# 2.net
KiCad netlist of a schematic drawn in Altium Designer
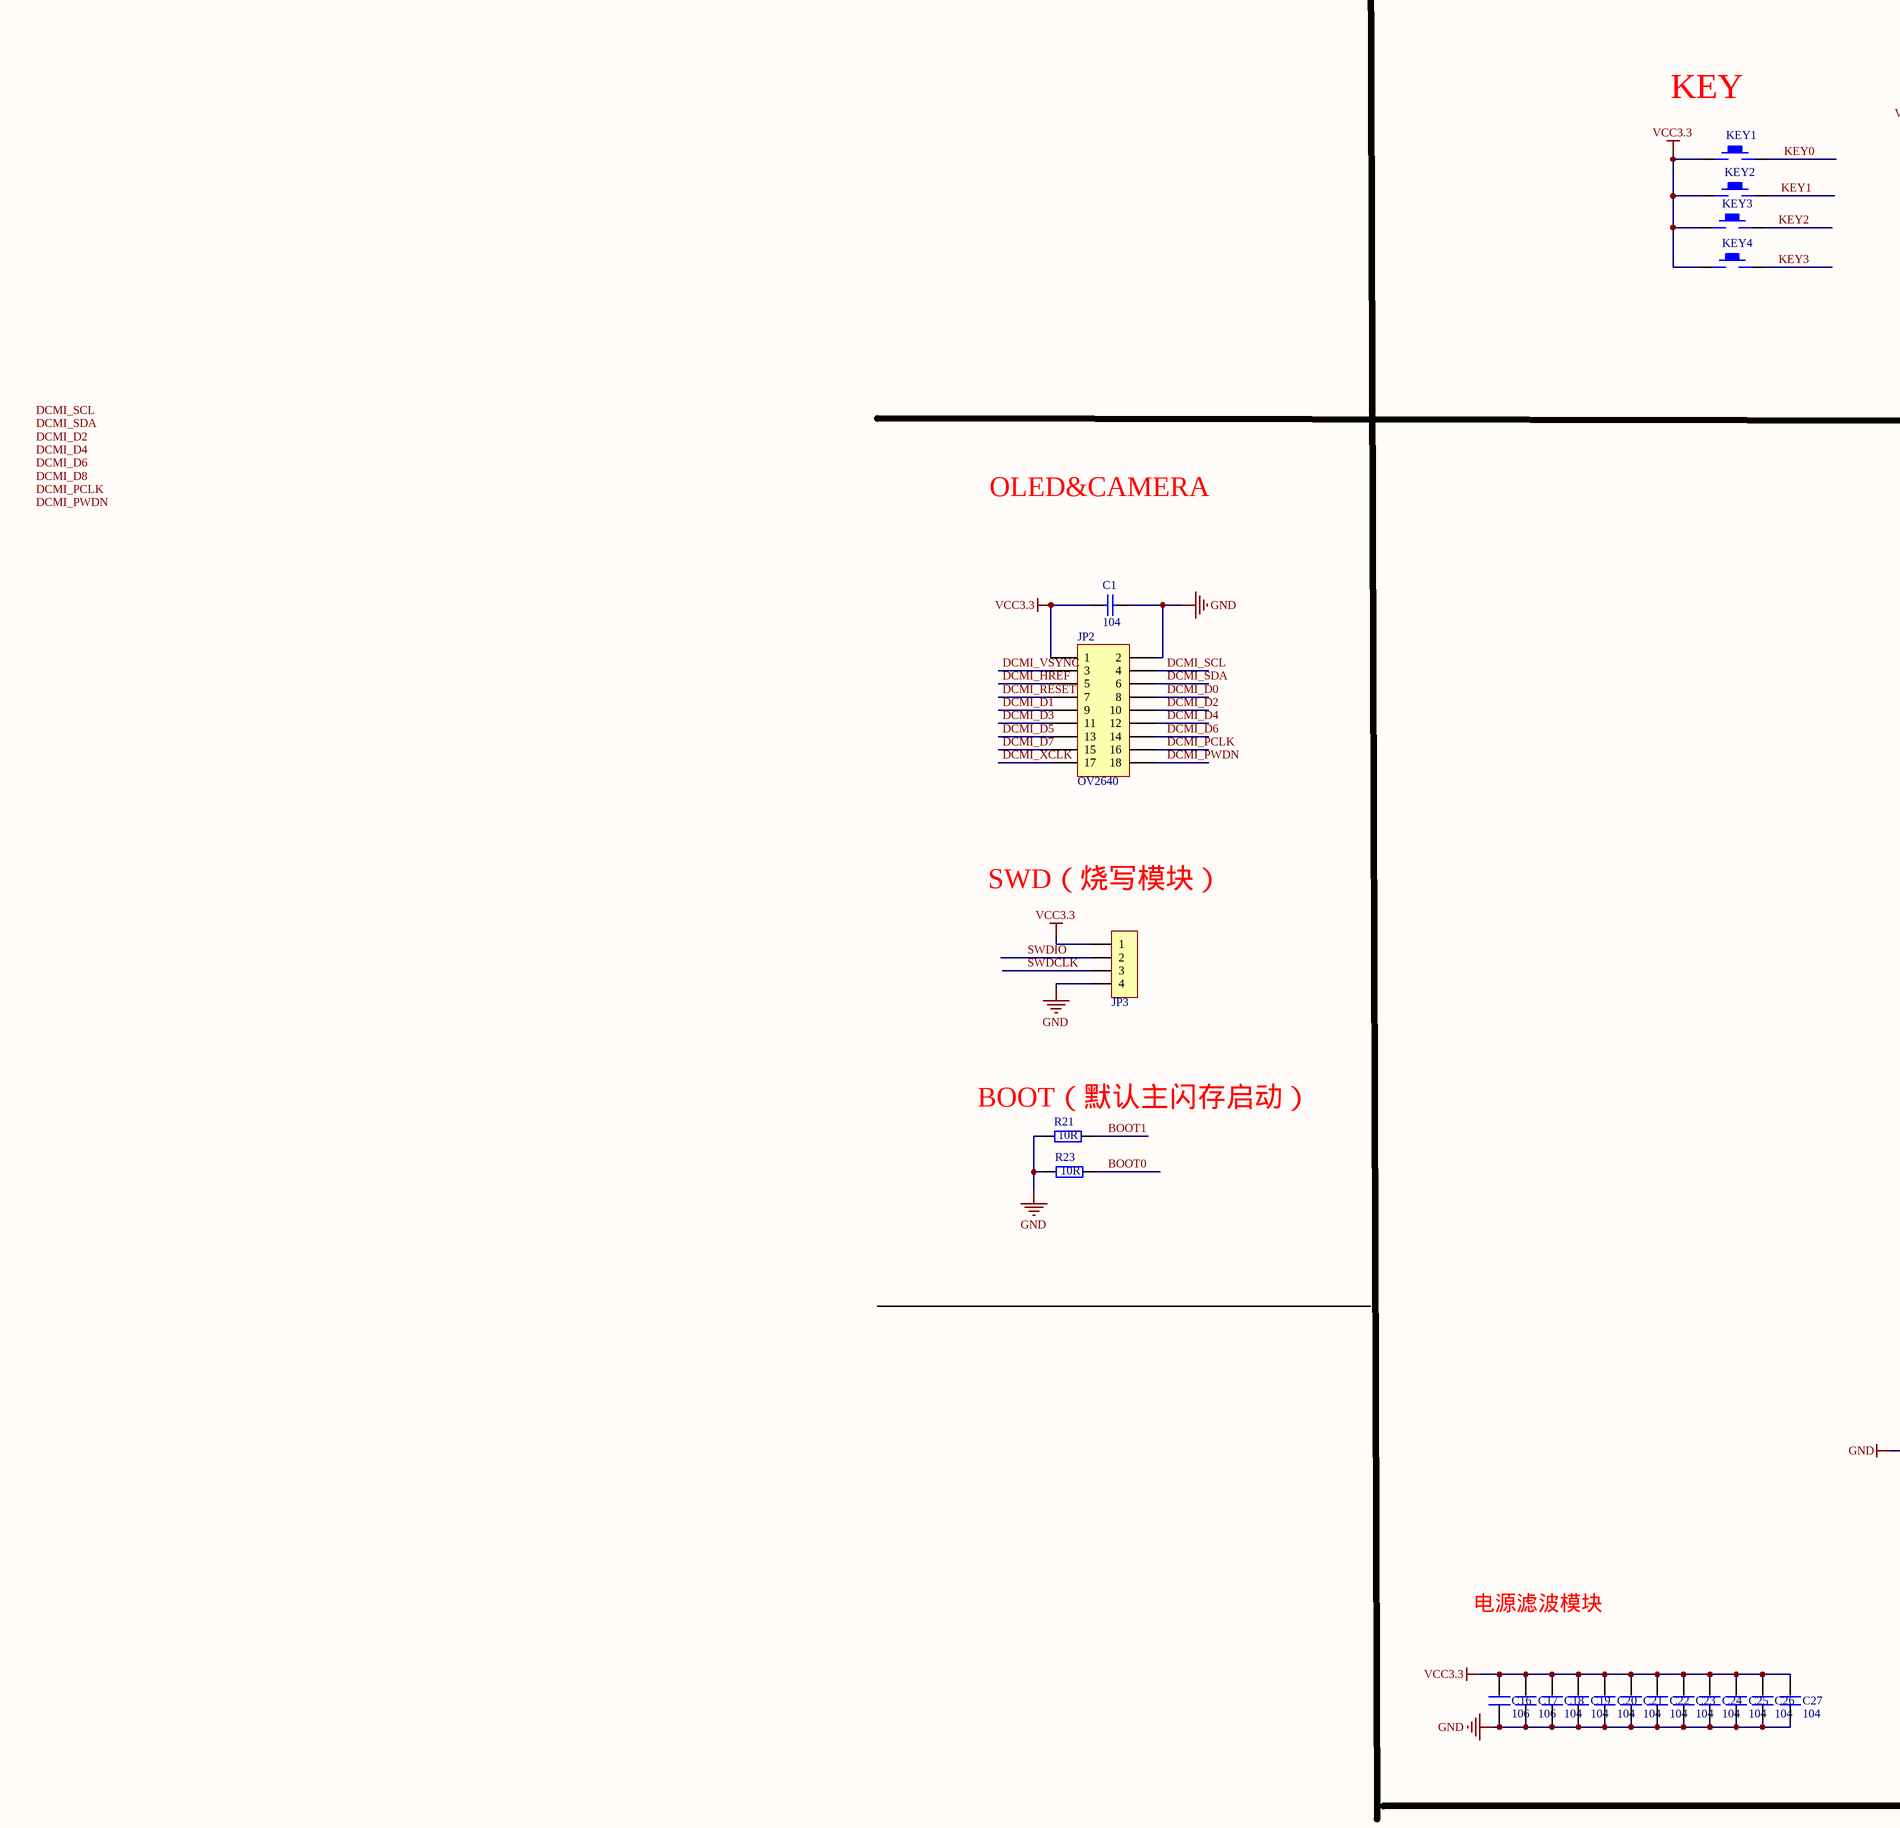
[diagram p0: 练一练2.SchDoc, left]
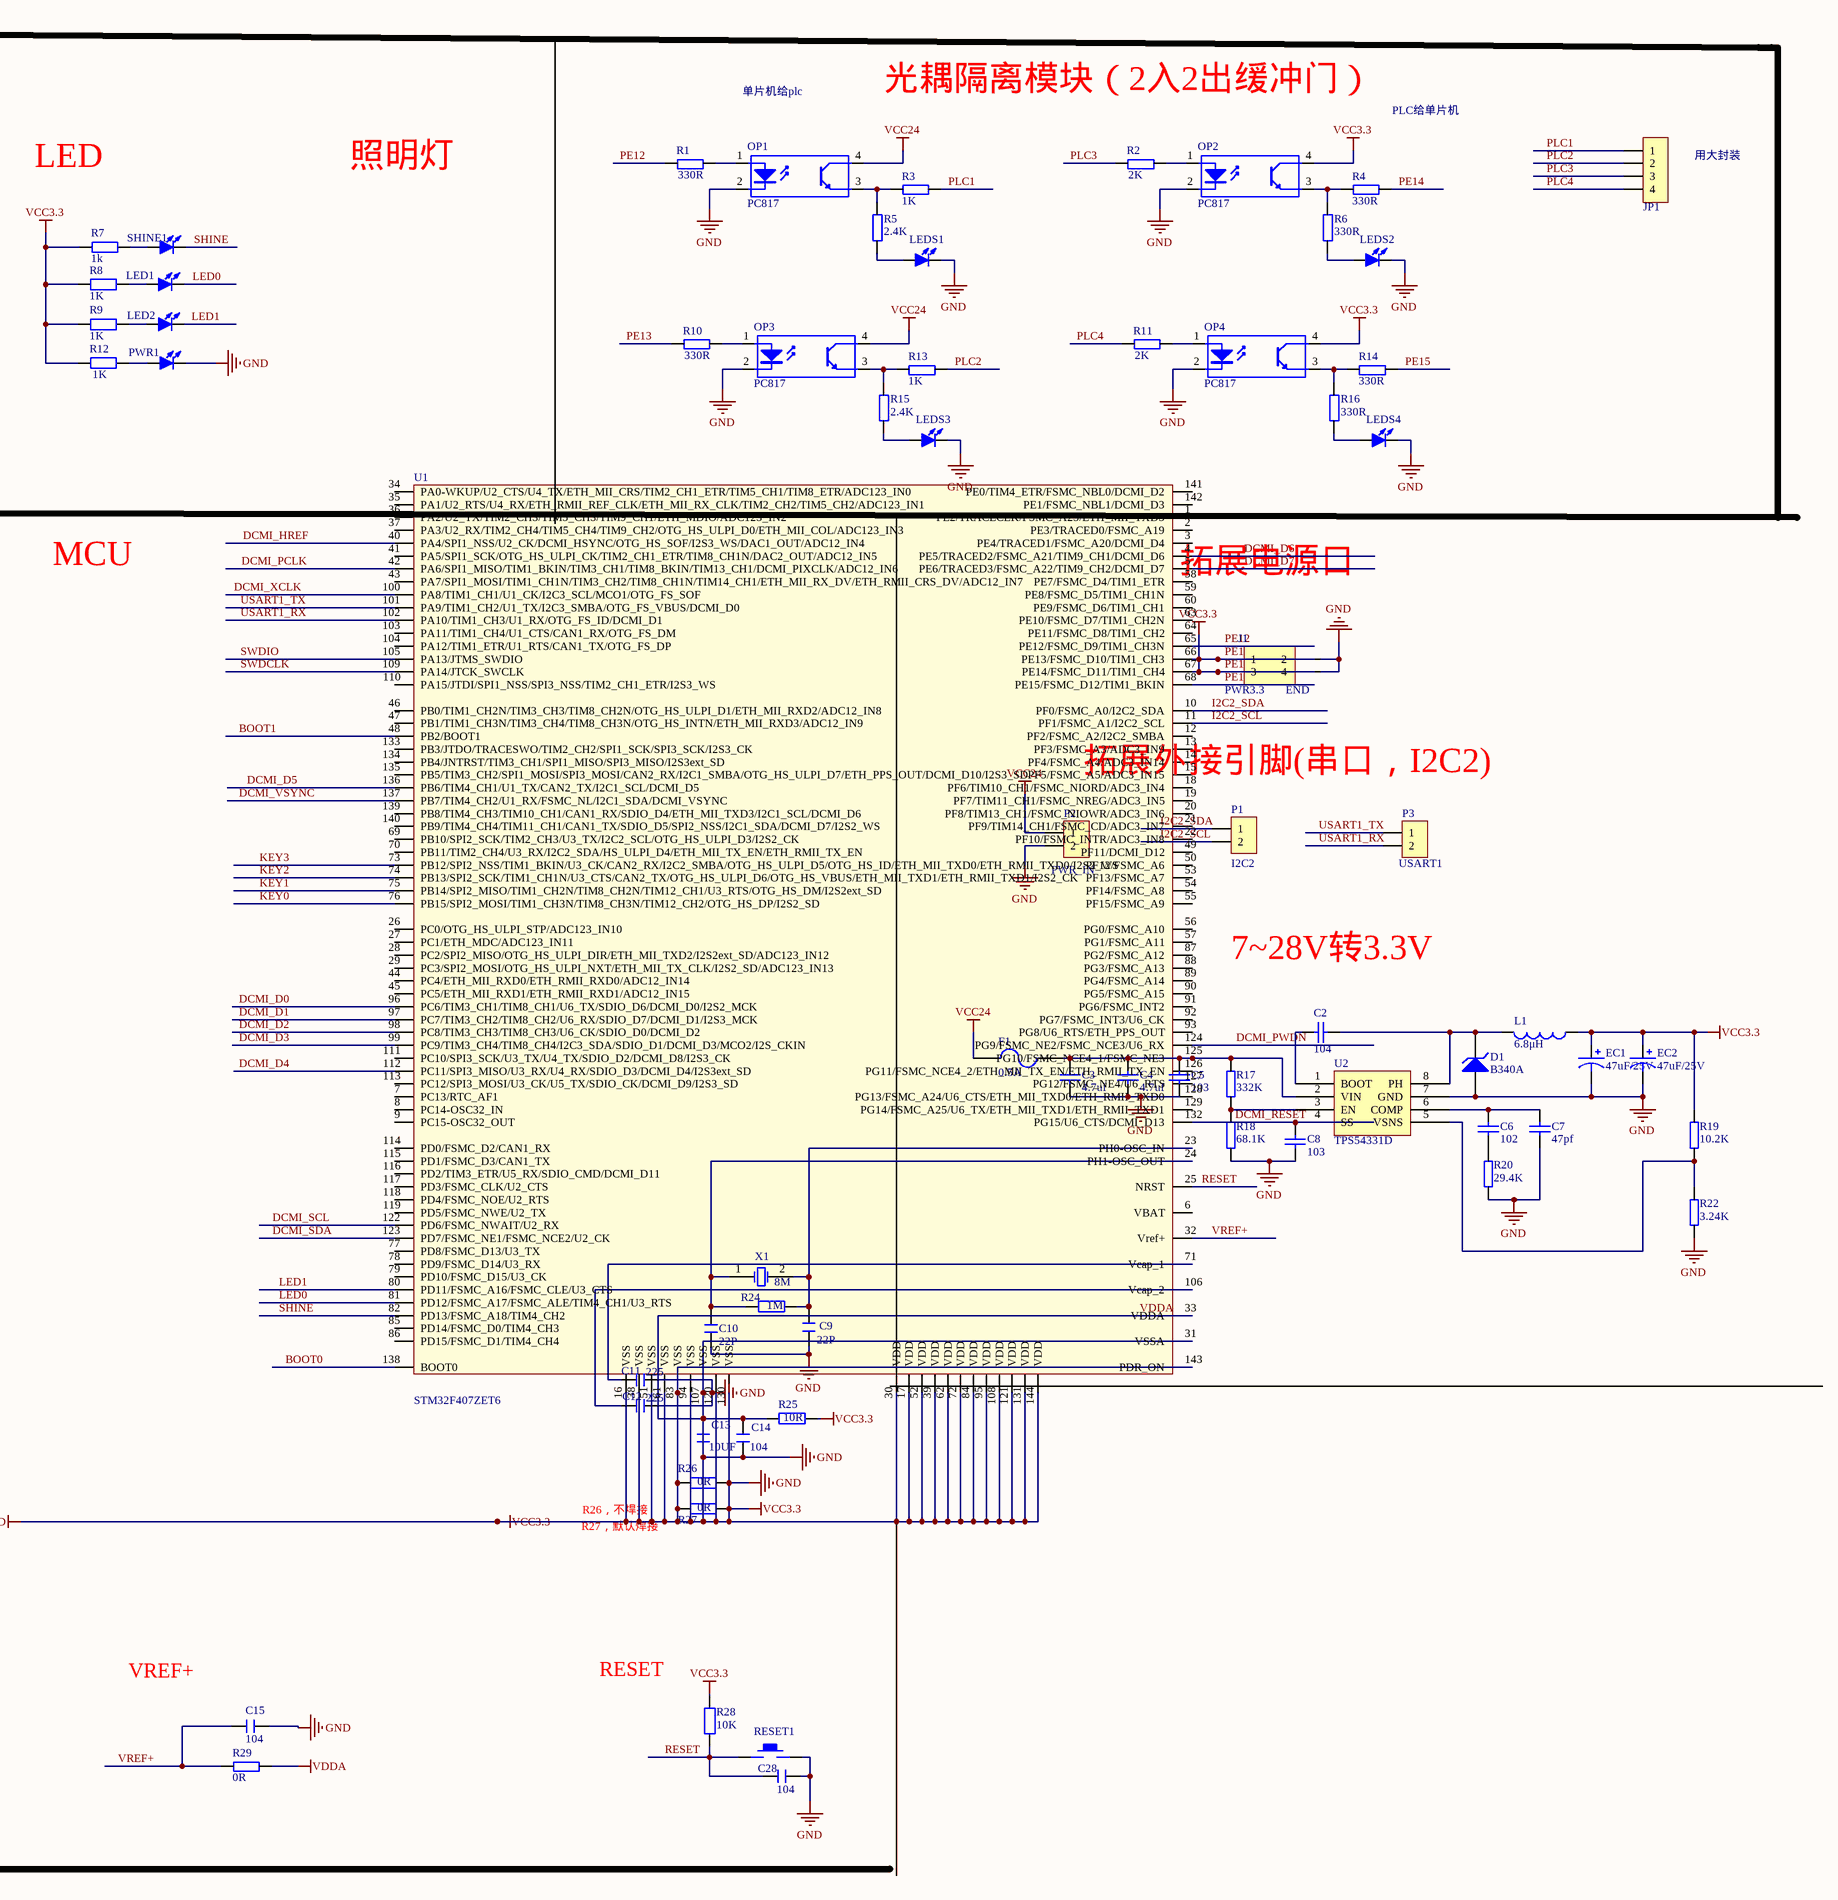
[diagram p1: 练一练2.SchDoc, right]

(export (version "E")
  (design (tool "Eeschema 10.0.6"))
  (components
    (comp (ref "C1")
      (value "104")
      (footprint "C0805")
      (description "Default Capacitor")
      (fields (field (name "PUBLISHER") "Altium Limited"))
      (libsource (lib "Lib_Devices_V1.0") (part "Cap0"))
    )
    (comp (ref "C2")
      (value "104")
      (footprint "C0805")
      (description "Default Capacitor")
      (fields (field (name "PUBLISHER") "Altium Limited"))
      (libsource (lib "Lib_Devices_V1.0") (part "Cap0"))
    )
    (comp (ref "C3")
      (value "4.7uf")
      (footprint "C0805")
      (description "Default Capacitor")
      (fields (field (name "PUBLISHER") "Altium Limited"))
      (libsource (lib "Lib_Devices_V1.0") (part "Cap0"))
    )
    (comp (ref "C4")
      (value "4.7uf")
      (footprint "C0805")
      (description "Default Capacitor")
      (fields (field (name "PUBLISHER") "Altium Limited"))
      (libsource (lib "Lib_Devices_V1.0") (part "Cap0"))
    )
    (comp (ref "C5")
      (value "103")
      (footprint "C0805")
      (description "Default Capacitor")
      (fields (field (name "PUBLISHER") "Altium Limited"))
      (libsource (lib "Lib_Devices_V1.0") (part "Cap0"))
    )
    (comp (ref "C6")
      (value "102")
      (footprint "C0805")
      (description "Default Capacitor")
      (fields (field (name "PUBLISHER") "Altium Limited"))
      (libsource (lib "Lib_Devices_V1.0") (part "Cap0"))
    )
    (comp (ref "C7")
      (value "47pf")
      (footprint "C0805")
      (description "Default Capacitor")
      (fields (field (name "PUBLISHER") "Altium Limited"))
      (libsource (lib "Lib_Devices_V1.0") (part "Cap0"))
    )
    (comp (ref "C8")
      (value "103")
      (footprint "C0805")
      (description "Default Capacitor")
      (fields (field (name "PUBLISHER") "Altium Limited"))
      (libsource (lib "Lib_Devices_V1.0") (part "Cap0"))
    )
    (comp (ref "C9")
      (value "22P")
      (footprint "C 0805")
      (description "无极性贴片电容")
      (fields (field (name "版权归属") "源创客"))
      (libsource (lib "STM32F407_CORE_BOARD") (part "C"))
    )
    (comp (ref "C10")
      (value "22P")
      (footprint "C 0805")
      (description "无极性贴片电容")
      (fields (field (name "版权归属") "源创客"))
      (libsource (lib "STM32F407_CORE_BOARD") (part "C"))
    )
    (comp (ref "C11")
      (value "225")
      (footprint "C 0805")
      (description "无极性贴片电容")
      (fields (field (name "版权归属") "源创客"))
      (libsource (lib "STM32F407_CORE_BOARD") (part "C"))
    )
    (comp (ref "C12")
      (value "225")
      (footprint "C 0805")
      (description "无极性贴片电容")
      (fields (field (name "版权归属") "源创客"))
      (libsource (lib "STM32F407_CORE_BOARD") (part "C"))
    )
    (comp (ref "C13")
      (value "10UF")
      (footprint "C 0805")
      (description "无极性贴片电容")
      (fields (field (name "版权归属") "源创客"))
      (libsource (lib "STM32F407_CORE_BOARD") (part "C"))
    )
    (comp (ref "C14")
      (value "104")
      (footprint "C 0805")
      (description "无极性贴片电容")
      (fields (field (name "版权归属") "源创客"))
      (libsource (lib "STM32F407_CORE_BOARD") (part "C"))
    )
    (comp (ref "C15")
      (value "104")
      (footprint "C 0805")
      (description "无极性贴片电容")
      (fields (field (name "版权归属") "源创客"))
      (libsource (lib "STM32F407_CORE_BOARD") (part "C"))
    )
    (comp (ref "C16")
      (value "106")
      (footprint "C 0805")
      (libsource (lib "Explorer STM32F407封装库_SCH") (part "C"))
    )
    (comp (ref "C17")
      (value "106")
      (footprint "C 0805")
      (libsource (lib "Explorer STM32F407封装库_SCH") (part "C"))
    )
    (comp (ref "C18")
      (value "104")
      (footprint "C 0805")
      (libsource (lib "Explorer STM32F407封装库_SCH") (part "C"))
    )
    (comp (ref "C19")
      (value "104")
      (footprint "C 0805")
      (libsource (lib "Explorer STM32F407封装库_SCH") (part "C"))
    )
    (comp (ref "C20")
      (value "104")
      (footprint "C 0805")
      (libsource (lib "Explorer STM32F407封装库_SCH") (part "C"))
    )
    (comp (ref "C21")
      (value "104")
      (footprint "C 0805")
      (libsource (lib "Explorer STM32F407封装库_SCH") (part "C"))
    )
    (comp (ref "C22")
      (value "104")
      (footprint "C 0805")
      (libsource (lib "Explorer STM32F407封装库_SCH") (part "C"))
    )
    (comp (ref "C23")
      (value "104")
      (footprint "C 0805")
      (libsource (lib "Explorer STM32F407封装库_SCH") (part "C"))
    )
    (comp (ref "C24")
      (value "104")
      (footprint "C 0805")
      (libsource (lib "Explorer STM32F407封装库_SCH") (part "C"))
    )
    (comp (ref "C25")
      (value "104")
      (footprint "C 0805")
      (libsource (lib "Explorer STM32F407封装库_SCH") (part "C"))
    )
    (comp (ref "C26")
      (value "104")
      (footprint "C 0805")
      (libsource (lib "Explorer STM32F407封装库_SCH") (part "C"))
    )
    (comp (ref "C27")
      (value "104")
      (footprint "C 0805")
      (libsource (lib "Explorer STM32F407封装库_SCH") (part "C"))
    )
    (comp (ref "C28")
      (value "104")
      (footprint "C 0805")
      (description "无极性贴片电容")
      (fields (field (name "版权归属") "源创客"))
      (libsource (lib "STM32F407_CORE_BOARD") (part "C"))
    )
    (comp (ref "D1")
      (value "B340A")
      (footprint "SMA")
      (description "瞬态抑制二极管")
      (fields (field (name "PUBLISHER") "Altium Limited"))
      (libsource (lib "Lib_Devices_V1.0") (part "D Zener"))
    )
    (comp (ref "EC1")
      (value "47uF/25V")
      (footprint "C-7")
      (description "Polarized Capacitor (Axial)")
      (fields (field (name "PUBLISHER") "Altium Limited"))
      (libsource (lib "Lib_Devices_V1.0") (part "Cap2"))
    )
    (comp (ref "EC2")
      (value "47uF/25V")
      (footprint "C-7")
      (description "Polarized Capacitor (Axial)")
      (fields (field (name "PUBLISHER") "Altium Limited"))
      (libsource (lib "Lib_Devices_V1.0") (part "Cap2"))
    )
    (comp (ref "F1")
      (value "0.5A")
      (footprint "FUSE0.5A")
      (description "Fuse")
      (fields (field (name "PUBLISHER") "Altium Limited"))
      (libsource (lib "Lib_Devices_V1.0") (part "Fuse1"))
    )
    (comp (ref "J1")
      (value "PWR3.3       END")
      (footprint "HDR2X2")
      (description "Header, 2-Pin, Dual row")
      (fields (field (name "PUBLISHER") "Altium Limited"))
      (libsource (lib "练一练1") (part "Header 2X2"))
    )
    (comp (ref "JP1")
      (value "SWD")
      (footprint "IDC1X4-5.08")
      (description "4P接插件")
      (fields (field (name "版权归属") "源创客"))
      (libsource (lib "练一练1") (part "Header 4"))
    )
    (comp (ref "JP2")
      (value "OV2640")
      (footprint "HDR2X9")
      (description "Header, 9-Pin, Dual row")
      (fields (field (name "PUBLISHER") "Altium Limited"))
      (libsource (lib "Miscellaneous Connectors") (part "Header 9X2"))
    )
    (comp (ref "JP3")
      (value "SWD")
      (footprint "HDR1X4")
      (description "4P接插件")
      (fields (field (name "版权归属") "源创客"))
      (libsource (lib "STM32F407_CORE_BOARD") (part "Header 4"))
    )
    (comp (ref "KEY1") (value "KEY_M") (footprint "KEY-SMD1") (libsource (lib "练一练1") (part "KEY_M")))
    (comp (ref "KEY2") (value "KEY_M") (footprint "KEY-SMD1") (libsource (lib "练一练1") (part "KEY_M")))
    (comp (ref "KEY3") (value "KEY_M") (footprint "KEY-SMD1") (libsource (lib "练一练1") (part "KEY_M")))
    (comp (ref "KEY4") (value "KEY_M") (footprint "KEY-SMD1") (libsource (lib "练一练1") (part "KEY_M")))
    (comp (ref "L1")
      (value "6.8μH")
      (footprint "Hunter")
      (description "Inductor")
      (fields (field (name "PUBLISHER") "Altium Limited"))
      (libsource (lib "Lib_Devices_V1.0") (part "Inductor"))
    )
    (comp (ref "LED1")
      (value "~")
      (footprint "LED0805")
      (description "贴片LED")
      (fields (field (name "版权归属") "源创客"))
      (libsource (lib "STM32F407_CORE_BOARD") (part "LED-SMD"))
    )
    (comp (ref "LED2")
      (value "~")
      (footprint "LED0805")
      (description "贴片LED")
      (fields (field (name "版权归属") "源创客"))
      (libsource (lib "STM32F407_CORE_BOARD") (part "LED-SMD"))
    )
    (comp (ref "LEDS1")
      (value "~")
      (footprint "LED0805")
      (description "贴片LED")
      (fields (field (name "版权归属") "源创客"))
      (libsource (lib "STM32F407_CORE_BOARD") (part "LED-SMD"))
    )
    (comp (ref "LEDS2")
      (value "~")
      (footprint "LED0805")
      (description "贴片LED")
      (fields (field (name "版权归属") "源创客"))
      (libsource (lib "STM32F407_CORE_BOARD") (part "LED-SMD"))
    )
    (comp (ref "LEDS3")
      (value "~")
      (footprint "LED0805")
      (description "贴片LED")
      (fields (field (name "版权归属") "源创客"))
      (libsource (lib "STM32F407_CORE_BOARD") (part "LED-SMD"))
    )
    (comp (ref "LEDS4")
      (value "~")
      (footprint "LED0805")
      (description "贴片LED")
      (fields (field (name "版权归属") "源创客"))
      (libsource (lib "STM32F407_CORE_BOARD") (part "LED-SMD"))
    )
    (comp (ref "OP1")
      (value "PC817")
      (footprint "SMD-4")
      (description "4-Pin Phototransistor Optocoupler")
      (fields (field (name "PUBLISHER") "Altium Limited"))
      (libsource (lib "练一练1") (part "Optoisolator"))
    )
    (comp (ref "OP2")
      (value "PC817")
      (footprint "SMD-4")
      (description "4-Pin Phototransistor Optocoupler")
      (fields (field (name "PUBLISHER") "Altium Limited"))
      (libsource (lib "练一练1") (part "Optoisolator"))
    )
    (comp (ref "OP3")
      (value "PC817")
      (footprint "SMD-4")
      (description "4-Pin Phototransistor Optocoupler")
      (fields (field (name "PUBLISHER") "Altium Limited"))
      (libsource (lib "Lib_Devices_V1.0") (part "Optoisolator"))
    )
    (comp (ref "OP4")
      (value "PC817")
      (footprint "SMD-4")
      (description "4-Pin Phototransistor Optocoupler")
      (fields (field (name "PUBLISHER") "Altium Limited"))
      (libsource (lib "Lib_Devices_V1.0") (part "Optoisolator"))
    )
    (comp (ref "P1") (value "I2C2") (footprint "HDR1X2") (libsource (lib "练一练1") (part "Header 1x2")))
    (comp (ref "P2") (value "PWR_IN") (footprint "IDC1X2-5.08") (libsource (lib "练一练1") (part "Header 1x2")))
    (comp (ref "P3") (value "USART1") (footprint "HDR1X2") (libsource (lib "练一练1") (part "Header 1x2")))
    (comp (ref "PWR1")
      (value "~")
      (footprint "LED0805")
      (description "贴片LED")
      (fields (field (name "版权归属") "源创客"))
      (libsource (lib "STM32F407_CORE_BOARD") (part "LED-SMD"))
    )
    (comp (ref "R1") (value "330R") (footprint "R0805") (libsource (lib "练一练1") (part "R_1")))
    (comp (ref "R2") (value "2K") (footprint "R0805") (libsource (lib "练一练1") (part "R_1")))
    (comp (ref "R3") (value "1K") (footprint "R0805") (libsource (lib "练一练1") (part "R_3")))
    (comp (ref "R4") (value "330R") (footprint "R0805") (libsource (lib "练一练1") (part "R_3")))
    (comp (ref "R5") (value "2.4K") (footprint "R0805") (libsource (lib "练一练1") (part "R_3")))
    (comp (ref "R6") (value "330R") (footprint "R0805") (libsource (lib "练一练1") (part "R_3")))
    (comp (ref "R7")
      (value "1k")
      (footprint "R0805")
      (description "贴片电阻")
      (fields (field (name "版权归属") "源创客"))
      (libsource (lib "练一练1") (part "R"))
    )
    (comp (ref "R8")
      (value "1K")
      (footprint "R0805")
      (description "贴片电阻")
      (fields (field (name "版权归属") "源创客"))
      (libsource (lib "练一练1") (part "R"))
    )
    (comp (ref "R9")
      (value "1K")
      (footprint "R0805")
      (description "贴片电阻")
      (fields (field (name "版权归属") "源创客"))
      (libsource (lib "练一练1") (part "R"))
    )
    (comp (ref "R10") (value "330R") (footprint "R0805") (libsource (lib "练一练1") (part "R_1")))
    (comp (ref "R11") (value "2K") (footprint "R0805") (libsource (lib "练一练1") (part "R_1")))
    (comp (ref "R12")
      (value "1K")
      (footprint "R 0805")
      (description "贴片电阻")
      (fields (field (name "版权归属") "源创客"))
      (libsource (lib "STM32F407_CORE_BOARD") (part "R"))
    )
    (comp (ref "R13") (value "1K") (footprint "R0805") (libsource (lib "练一练1") (part "R_3")))
    (comp (ref "R14") (value "330R") (footprint "R0805") (libsource (lib "练一练1") (part "R_3")))
    (comp (ref "R15") (value "2.4K") (footprint "R0805") (libsource (lib "练一练1") (part "R_3")))
    (comp (ref "R16") (value "330R") (footprint "R0805") (libsource (lib "练一练1") (part "R_3")))
    (comp (ref "R17")
      (value "332K")
      (footprint "R0805")
      (description "default resistor")
      (libsource (lib "Lib_Devices_V1.0") (part "Res0"))
    )
    (comp (ref "R18")
      (value "68.1K")
      (footprint "R 0805")
      (description "default resistor")
      (libsource (lib "Lib_Devices_V1.0") (part "Res0"))
    )
    (comp (ref "R19")
      (value "10.2K")
      (footprint "R 0805")
      (description "default resistor")
      (libsource (lib "Lib_Devices_V1.0") (part "Res0"))
    )
    (comp (ref "R20")
      (value "29.4K")
      (footprint "R 0805")
      (description "default resistor")
      (libsource (lib "Lib_Devices_V1.0") (part "Res0"))
    )
    (comp (ref "R21")
      (value "10R")
      (footprint "R 0805")
      (description "贴片电阻")
      (fields (field (name "版权归属") "源创客"))
      (libsource (lib "STM32F407_CORE_BOARD") (part "R"))
    )
    (comp (ref "R22")
      (value "3.24K")
      (footprint "R0805")
      (description "default resistor")
      (libsource (lib "Lib_Devices_V1.0") (part "Res0"))
    )
    (comp (ref "R23")
      (value "10R")
      (footprint "R 0805")
      (description "贴片电阻")
      (fields (field (name "版权归属") "源创客"))
      (libsource (lib "STM32F407_CORE_BOARD") (part "R"))
    )
    (comp (ref "R24")
      (value "1M")
      (footprint "R 0805")
      (description "贴片电阻")
      (fields (field (name "版权归属") "源创客"))
      (libsource (lib "STM32F407_CORE_BOARD") (part "R"))
    )
    (comp (ref "R25")
      (value "10R")
      (footprint "R 0805")
      (description "贴片电阻")
      (fields (field (name "版权归属") "源创客"))
      (libsource (lib "STM32F407_CORE_BOARD") (part "R"))
    )
    (comp (ref "R26")
      (value "0R")
      (footprint "R 0805")
      (description "贴片电阻")
      (fields (field (name "版权归属") "源创客"))
      (libsource (lib "STM32F407_CORE_BOARD") (part "R"))
    )
    (comp (ref "R27")
      (value "0R")
      (footprint "R 0805")
      (description "贴片电阻")
      (fields (field (name "版权归属") "源创客"))
      (libsource (lib "STM32F407_CORE_BOARD") (part "R"))
    )
    (comp (ref "R28")
      (value "10K")
      (footprint "R 0805")
      (description "贴片电阻")
      (fields (field (name "版权归属") "源创客"))
      (libsource (lib "STM32F407_CORE_BOARD") (part "R"))
    )
    (comp (ref "R29") (value "0R") (footprint "R 0805") (libsource (lib "") (part "R_1")))
    (comp (ref "RESET1") (value "KEY_M") (footprint "KEY-SMD1") (libsource (lib "练一练1") (part "KEY_M")))
    (comp (ref "SHINE1")
      (value "~")
      (footprint "LED0805")
      (description "贴片LED")
      (fields (field (name "版权归属") "源创客"))
      (libsource (lib "STM32F407_CORE_BOARD") (part "LED-SMD"))
    )
    (comp (ref "U1")
      (value "STM32F407ZET6")
      (footprint "LQFP144 20X20_M")
      (libsource (lib "STM32F407_CORE_BOARD") (part "STM32F407ZET6"))
    )
    (comp (ref "U2")
      (value "TPS54331D")
      (footprint "SOP8DCDC")
      (description "TPS54331DDAR")
      (libsource (lib "Camera_Detection") (part "TPS54331DDAR"))
    )
    (comp (ref "X1")
      (value "8M")
      (footprint "49/S_N")
      (description "Crystal Oscillator")
      (fields (field (name "PUBLISHER") "*"))
      (libsource (lib "练一练1") (part "XTAL"))
    )
  )
  (nets
    (net (code "2") (name "/BOOT0") (class "Default")
      (node (ref "R23") (pin "2") (pinfunction "2_2") (pintype "passive"))
      (node (ref "U1") (pin "138") (pinfunction "BOOT0_138") (pintype "passive"))
    )
    (net (code "3") (name "/BOOT1") (class "Default")
      (node (ref "R21") (pin "2") (pinfunction "2_2") (pintype "passive"))
      (node (ref "U1") (pin "48") (pinfunction "PB2/BOOT1_48") (pintype "passive"))
    )
    (net (code "4") (name "/DCMI_D0") (class "Default")
      (node (ref "JP2") (pin "8") (pinfunction "8_8") (pintype "passive"))
      (node (ref "U1") (pin "96") (pinfunction "PC6/TIM3_CH1/TIM8_CH1/U6_TX/SDIO_D6/DCMI_D0/I2S2_MCK_96") (pintype "passive"))
    )
    (net (code "5") (name "/DCMI_D1") (class "Default")
      (node (ref "JP2") (pin "9") (pinfunction "9_9") (pintype "passive"))
      (node (ref "U1") (pin "97") (pinfunction "PC7/TIM3_CH2/TIM8_CH2/U6_RX/SDIO_D7/DCMI_D1/I2S3_MCK_97") (pintype "passive"))
    )
    (net (code "6") (name "/DCMI_D2") (class "Default")
      (node (ref "JP2") (pin "10") (pinfunction "10_10") (pintype "passive"))
      (node (ref "U1") (pin "98") (pinfunction "PC8/TIM3_CH3/TIM8_CH3/U6_CK/SDIO_D0/DCMI_D2_98") (pintype "passive"))
    )
    (net (code "7") (name "/DCMI_D3") (class "Default")
      (node (ref "JP2") (pin "11") (pinfunction "11_11") (pintype "passive"))
      (node (ref "U1") (pin "99") (pinfunction "PC9/TIM3_CH4/TIM8_CH4/I2C3_SDA/SDIO_D1/DCMI_D3/MCO2/I2S_CKIN_99") (pintype "passive"))
    )
    (net (code "8") (name "/DCMI_D4") (class "Default")
      (node (ref "JP2") (pin "12") (pinfunction "12_12") (pintype "passive"))
      (node (ref "U1") (pin "112") (pinfunction "PC11/SPI3_MISO/U3_RX/U4_RX/SDIO_D3/DCMI_D4/I2S3ext_SD_112") (pintype "passive"))
    )
    (net (code "9") (name "/DCMI_D5") (class "Default")
      (node (ref "JP2") (pin "13") (pinfunction "13_13") (pintype "passive"))
      (node (ref "U1") (pin "136") (pinfunction "PB6/TIM4_CH1/U1_TX/CAN2_TX/I2C1_SCL/DCMI_D5_136") (pintype "passive"))
    )
    (net (code "10") (name "/DCMI_D6") (class "Default")
      (node (ref "JP2") (pin "14") (pinfunction "14_14") (pintype "passive"))
      (node (ref "U1") (pin "4") (pinfunction "PE5/TRACED2/FSMC_A21/TIM9_CH1/DCMI_D6_4") (pintype "passive"))
    )
    (net (code "11") (name "/DCMI_D7") (class "Default")
      (node (ref "JP2") (pin "15") (pinfunction "15_15") (pintype "passive"))
      (node (ref "U1") (pin "5") (pinfunction "PE6/TRACED3/FSMC_A22/TIM9_CH2/DCMI_D7_5") (pintype "passive"))
    )
    (net (code "13") (name "/DCMI_HREF") (class "Default")
      (node (ref "JP2") (pin "5") (pinfunction "5_5") (pintype "passive"))
      (node (ref "U1") (pin "40") (pinfunction "PA4/SPI1_NSS/U2_CK/DCMI_HSYNC/OTG_HS_SOF/I2S3_WS/DAC1_OUT/ADC12_IN4_40") (pintype "passive"))
    )
    (net (code "14") (name "/DCMI_PCLK") (class "Default")
      (node (ref "JP2") (pin "16") (pinfunction "16_16") (pintype "passive"))
      (node (ref "U1") (pin "42") (pinfunction "PA6/SPI1_MISO/TIM1_BKIN/TIM3_CH1/TIM8_BKIN/TIM13_CH1/DCMI_PIXCLK/ADC12_IN6_42") (pintype "passive"))
    )
    (net (code "15") (name "/DCMI_PWDN") (class "Default")
      (node (ref "JP2") (pin "18") (pinfunction "18_18") (pintype "passive"))
      (node (ref "U1") (pin "124") (pinfunction "PG9/FSMC_NE2/FSMC_NCE3/U6_RX_124") (pintype "passive"))
    )
    (net (code "16") (name "/DCMI_RESET") (class "Default")
      (node (ref "C8") (pin "1") (pinfunction "1_1") (pintype "passive"))
      (node (ref "JP2") (pin "7") (pinfunction "7_7") (pintype "passive"))
      (node (ref "U1") (pin "132") (pinfunction "PG15/U6_CTS/DCMI_D13_132") (pintype "passive"))
      (node (ref "U2") (pin "4") (pinfunction "SS_4") (pintype "passive"))
    )
    (net (code "17") (name "/DCMI_SCL") (class "Default")
      (node (ref "JP2") (pin "4") (pinfunction "4_4") (pintype "passive"))
      (node (ref "U1") (pin "122") (pinfunction "PD6/FSMC_NWAIT/U2_RX_122") (pintype "passive"))
    )
    (net (code "18") (name "/DCMI_SDA") (class "Default")
      (node (ref "JP2") (pin "6") (pinfunction "6_6") (pintype "passive"))
      (node (ref "U1") (pin "123") (pinfunction "PD7/FSMC_NE1/FSMC_NCE2/U2_CK_123") (pintype "passive"))
    )
    (net (code "19") (name "/DCMI_VSYNC") (class "Default")
      (node (ref "JP2") (pin "3") (pinfunction "3_3") (pintype "passive"))
      (node (ref "U1") (pin "137") (pinfunction "PB7/TIM4_CH2/U1_RX/FSMC_NL/I2C1_SDA/DCMI_VSYNC_137") (pintype "passive"))
    )
    (net (code "20") (name "/DCMI_XCLK") (class "Default")
      (node (ref "JP2") (pin "17") (pinfunction "17_17") (pintype "passive"))
      (node (ref "U1") (pin "100") (pinfunction "PA8/TIM1_CH1/U1_CK/I2C3_SCL/MCO1/OTG_FS_SOF_100") (pintype "passive"))
    )
    (net (code "21") (name "/I2C2_SCL") (class "Default")
      (node (ref "P1") (pin "2") (pinfunction "2_2") (pintype "passive"))
      (node (ref "U1") (pin "11") (pinfunction "PF1/FSMC_A1/I2C2_SCL_11") (pintype "passive"))
    )
    (net (code "22") (name "/I2C2_SDA") (class "Default")
      (node (ref "P1") (pin "1") (pinfunction "1_1") (pintype "passive"))
      (node (ref "U1") (pin "10") (pinfunction "PF0/FSMC_A0/I2C2_SDA_10") (pintype "passive"))
    )
    (net (code "23") (name "/KEY0") (class "Default")
      (node (ref "KEY1") (pin "2") (pinfunction "2_2") (pintype "passive"))
      (node (ref "U1") (pin "76") (pinfunction "PB15/SPI2_MOSI/TIM1_CH3N/TIM8_CH3N/TIM12_CH2/OTG_HS_DP/I2S2_SD_76") (pintype "passive"))
    )
    (net (code "24") (name "/KEY1") (class "Default")
      (node (ref "KEY2") (pin "2") (pinfunction "2_2") (pintype "passive"))
      (node (ref "U1") (pin "75") (pinfunction "PB14/SPI2_MISO/TIM1_CH2N/TIM8_CH2N/TIM12_CH1/U3_RTS/OTG_HS_DM/I2S2ext_SD_75") (pintype "passive"))
    )
    (net (code "25") (name "/KEY2") (class "Default")
      (node (ref "KEY3") (pin "2") (pinfunction "2_2") (pintype "passive"))
      (node (ref "U1") (pin "74") (pinfunction "PB13/SPI2_SCK/TIM1_CH1N/U3_CTS/CAN2_TX/OTG_HS_ULPI_D6/OTG_HS_VBUS/ETH_MII_TXD1/ETH_RMII_TXD1/I2S2_CK_74") (pintype "passive"))
    )
    (net (code "26") (name "/KEY3") (class "Default")
      (node (ref "KEY4") (pin "2") (pinfunction "2_2") (pintype "passive"))
      (node (ref "U1") (pin "73") (pinfunction "PB12/SPI2_NSS/TIM1_BKIN/U3_CK/CAN2_RX/I2C2_SMBA/OTG_HS_ULPI_D5/OTG_HS_ID/ETH_MII_TXD0/ETH_RMII_TXD0/I2S2_WS_73") (pintype "passive"))
    )
    (net (code "27") (name "/LED0") (class "Default")
      (node (ref "LED1") (pin "2") (pinfunction "K_2") (pintype "passive"))
      (node (ref "U1") (pin "81") (pinfunction "PD12/FSMC_A17/FSMC_ALE/TIM4_CH1/U3_RTS_81") (pintype "passive"))
    )
    (net (code "28") (name "/LED1") (class "Default")
      (node (ref "LED2") (pin "2") (pinfunction "K_2") (pintype "passive"))
      (node (ref "U1") (pin "80") (pinfunction "PD11/FSMC_A16/FSMC_CLE/U3_CTS_80") (pintype "passive"))
    )
    (net (code "29") (name "/PE12") (class "Default")
      (node (ref "R1") (pin "1") (pintype "passive"))
      (node (ref "U1") (pin "65") (pinfunction "PE12/FSMC_D9/TIM1_CH3N_65") (pintype "passive"))
    )
    (net (code "30") (name "/PE15") (class "Default")
      (node (ref "R14") (pin "2") (pintype "passive"))
      (node (ref "U1") (pin "68") (pinfunction "PE15/FSMC_D12/TIM1_BKIN_68") (pintype "passive"))
    )
    (net (code "31") (name "/PLC1") (class "Default")
      (node (ref "JP1") (pin "1") (pinfunction "1_1") (pintype "passive"))
      (node (ref "R3") (pin "2") (pintype "passive"))
    )
    (net (code "32") (name "/PLC2") (class "Default")
      (node (ref "JP1") (pin "2") (pinfunction "2_2") (pintype "passive"))
      (node (ref "R13") (pin "2") (pintype "passive"))
    )
    (net (code "33") (name "/PLC3") (class "Default")
      (node (ref "JP1") (pin "3") (pinfunction "3_3") (pintype "passive"))
      (node (ref "R2") (pin "1") (pintype "passive"))
    )
    (net (code "34") (name "/PLC4") (class "Default")
      (node (ref "JP1") (pin "4") (pinfunction "4_4") (pintype "passive"))
      (node (ref "R11") (pin "1") (pintype "passive"))
    )
    (net (code "35") (name "/RESET") (class "Default")
      (node (ref "C28") (pin "2") (pinfunction "2_2") (pintype "passive"))
      (node (ref "R28") (pin "1") (pinfunction "1_1") (pintype "passive"))
      (node (ref "RESET1") (pin "1") (pinfunction "1_1") (pintype "passive"))
      (node (ref "U1") (pin "25") (pinfunction "NRST_25") (pintype "passive"))
    )
    (net (code "36") (name "/SHINE") (class "Default")
      (node (ref "SHINE1") (pin "2") (pinfunction "K_2") (pintype "passive"))
      (node (ref "U1") (pin "82") (pinfunction "PD13/FSMC_A18/TIM4_CH2_82") (pintype "passive"))
    )
    (net (code "37") (name "/SWDCLK") (class "Default")
      (node (ref "JP3") (pin "3") (pinfunction "3_3") (pintype "passive"))
      (node (ref "U1") (pin "109") (pinfunction "PA14/JTCK_SWCLK_109") (pintype "passive"))
    )
    (net (code "38") (name "/SWDIO") (class "Default")
      (node (ref "JP3") (pin "2") (pinfunction "2_2") (pintype "passive"))
      (node (ref "U1") (pin "105") (pinfunction "PA13/JTMS_SWDIO_105") (pintype "passive"))
    )
    (net (code "39") (name "/USART1_RX") (class "Default")
      (node (ref "P3") (pin "2") (pinfunction "2_2") (pintype "passive"))
      (node (ref "U1") (pin "102") (pinfunction "PA10/TIM1_CH3/U1_RX/OTG_FS_ID/DCMI_D1_102") (pintype "passive"))
    )
    (net (code "40") (name "/USART1_TX") (class "Default")
      (node (ref "P3") (pin "1") (pinfunction "1_1") (pintype "passive"))
      (node (ref "U1") (pin "101") (pinfunction "PA9/TIM1_CH2/U1_TX/I2C3_SMBA/OTG_FS_VBUS/DCMI_D0_101") (pintype "passive"))
    )
    (net (code "41") (name "/VREF+") (class "Default")
      (node (ref "C15") (pin "2") (pinfunction "2_2") (pintype "passive"))
      (node (ref "R29") (pin "1") (pintype "passive"))
      (node (ref "U1") (pin "32") (pinfunction "Vref+_32") (pintype "passive"))
    )
    (net (code "42") (name "GND") (class "Default")
      (node (ref "C1") (pin "1") (pinfunction "1_1") (pintype "passive"))
      (node (ref "C1") (pin "2") (pinfunction "2_2") (pintype "passive"))
      (node (ref "C10") (pin "1") (pinfunction "1_1") (pintype "passive"))
      (node (ref "C11") (pin "2") (pinfunction "2_2") (pintype "passive"))
      (node (ref "C12") (pin "2") (pinfunction "2_2") (pintype "passive"))
      (node (ref "C13") (pin "1") (pinfunction "1_1") (pintype "passive"))
      (node (ref "C13") (pin "2") (pinfunction "2_2") (pintype "passive"))
      (node (ref "C14") (pin "1") (pinfunction "1_1") (pintype "passive"))
      (node (ref "C14") (pin "2") (pinfunction "2_2") (pintype "passive"))
      (node (ref "C15") (pin "1") (pinfunction "1_1") (pintype "passive"))
      (node (ref "C16") (pin "1") (pintype "passive"))
      (node (ref "C16") (pin "2") (pintype "passive"))
      (node (ref "C17") (pin "1") (pintype "passive"))
      (node (ref "C17") (pin "2") (pintype "passive"))
      (node (ref "C18") (pin "1") (pintype "passive"))
      (node (ref "C18") (pin "2") (pintype "passive"))
      (node (ref "C19") (pin "1") (pintype "passive"))
      (node (ref "C19") (pin "2") (pintype "passive"))
      (node (ref "C20") (pin "1") (pintype "passive"))
      (node (ref "C20") (pin "2") (pintype "passive"))
      (node (ref "C21") (pin "1") (pintype "passive"))
      (node (ref "C21") (pin "2") (pintype "passive"))
      (node (ref "C22") (pin "1") (pintype "passive"))
      (node (ref "C22") (pin "2") (pintype "passive"))
      (node (ref "C23") (pin "1") (pintype "passive"))
      (node (ref "C23") (pin "2") (pintype "passive"))
      (node (ref "C24") (pin "1") (pintype "passive"))
      (node (ref "C24") (pin "2") (pintype "passive"))
      (node (ref "C25") (pin "1") (pintype "passive"))
      (node (ref "C25") (pin "2") (pintype "passive"))
      (node (ref "C26") (pin "1") (pintype "passive"))
      (node (ref "C26") (pin "2") (pintype "passive"))
      (node (ref "C27") (pin "1") (pintype "passive"))
      (node (ref "C27") (pin "2") (pintype "passive"))
      (node (ref "C28") (pin "1") (pinfunction "1_1") (pintype "passive"))
      (node (ref "C3") (pin "2") (pinfunction "2_2") (pintype "passive"))
      (node (ref "C4") (pin "2") (pinfunction "2_2") (pintype "passive"))
      (node (ref "C5") (pin "2") (pinfunction "2_2") (pintype "passive"))
      (node (ref "C7") (pin "2") (pinfunction "2_2") (pintype "passive"))
      (node (ref "C8") (pin "2") (pinfunction "2_2") (pintype "passive"))
      (node (ref "C9") (pin "1") (pinfunction "1_1") (pintype "passive"))
      (node (ref "D1") (pin "1") (pinfunction "A_1") (pintype "passive"))
      (node (ref "EC1") (pin "1") (pinfunction "1_1") (pintype "passive"))
      (node (ref "EC1") (pin "2") (pinfunction "2_2") (pintype "passive"))
      (node (ref "EC2") (pin "1") (pinfunction "1_1") (pintype "passive"))
      (node (ref "EC2") (pin "2") (pinfunction "2_2") (pintype "passive"))
      (node (ref "J1") (pin "1") (pinfunction "1_1") (pintype "passive"))
      (node (ref "J1") (pin "2") (pinfunction "2_2") (pintype "passive"))
      (node (ref "J1") (pin "3") (pinfunction "3_3") (pintype "passive"))
      (node (ref "J1") (pin "4") (pinfunction "4_4") (pintype "passive"))
      (node (ref "JP2") (pin "1") (pinfunction "1_1") (pintype "passive"))
      (node (ref "JP2") (pin "2") (pinfunction "2_2") (pintype "passive"))
      (node (ref "JP3") (pin "1") (pinfunction "1_1") (pintype "passive"))
      (node (ref "JP3") (pin "4") (pinfunction "4_4") (pintype "passive"))
      (node (ref "KEY1") (pin "1") (pinfunction "1_1") (pintype "passive"))
      (node (ref "KEY2") (pin "1") (pinfunction "1_1") (pintype "passive"))
      (node (ref "KEY3") (pin "1") (pinfunction "1_1") (pintype "passive"))
      (node (ref "KEY4") (pin "1") (pinfunction "1_1") (pintype "passive"))
      (node (ref "L1") (pin "1") (pinfunction "1_1") (pintype "passive"))
      (node (ref "LEDS1") (pin "2") (pinfunction "K_2") (pintype "passive"))
      (node (ref "LEDS2") (pin "2") (pinfunction "K_2") (pintype "passive"))
      (node (ref "LEDS3") (pin "2") (pinfunction "K_2") (pintype "passive"))
      (node (ref "LEDS4") (pin "2") (pinfunction "K_2") (pintype "passive"))
      (node (ref "OP1") (pin "2") (pinfunction "K_2") (pintype "passive"))
      (node (ref "OP2") (pin "2") (pinfunction "K_2") (pintype "passive"))
      (node (ref "OP2") (pin "4") (pinfunction "C_4") (pintype "passive"))
      (node (ref "OP3") (pin "2") (pinfunction "K_2") (pintype "passive"))
      (node (ref "OP4") (pin "2") (pinfunction "K_2") (pintype "passive"))
      (node (ref "OP4") (pin "4") (pinfunction "C_4") (pintype "passive"))
      (node (ref "P2") (pin "2") (pinfunction "2_2") (pintype "passive"))
      (node (ref "PWR1") (pin "2") (pinfunction "K_2") (pintype "passive"))
      (node (ref "R10") (pin "1") (pintype "passive"))
      (node (ref "R12") (pin "1") (pinfunction "1_1") (pintype "passive"))
      (node (ref "R18") (pin "1") (pinfunction "1_1") (pintype "passive"))
      (node (ref "R19") (pin "2") (pinfunction "2_2") (pintype "passive"))
      (node (ref "R20") (pin "2") (pinfunction "2_2") (pintype "passive"))
      (node (ref "R21") (pin "1") (pinfunction "1_1") (pintype "passive"))
      (node (ref "R22") (pin "1") (pinfunction "1_1") (pintype "passive"))
      (node (ref "R23") (pin "1") (pinfunction "1_1") (pintype "passive"))
      (node (ref "R25") (pin "1") (pinfunction "1_1") (pintype "passive"))
      (node (ref "R25") (pin "2") (pinfunction "2_2") (pintype "passive"))
      (node (ref "R26") (pin "1") (pinfunction "1_1") (pintype "passive"))
      (node (ref "R26") (pin "2") (pinfunction "2_2") (pintype "passive"))
      (node (ref "R27") (pin "1") (pinfunction "1_1") (pintype "passive"))
      (node (ref "R27") (pin "2") (pinfunction "2_2") (pintype "passive"))
      (node (ref "R28") (pin "2") (pinfunction "2_2") (pintype "passive"))
      (node (ref "R29") (pin "2") (pintype "passive"))
      (node (ref "R4") (pin "2") (pintype "passive"))
      (node (ref "R7") (pin "1") (pinfunction "1_1") (pintype "passive"))
      (node (ref "R8") (pin "1") (pinfunction "1_1") (pintype "passive"))
      (node (ref "R9") (pin "1") (pinfunction "1_1") (pintype "passive"))
      (node (ref "RESET1") (pin "2") (pinfunction "2_2") (pintype "passive"))
      (node (ref "U1") (pin "107") (pinfunction "VSS_107") (pintype "passive"))
      (node (ref "U1") (pin "108") (pinfunction "VDD_108") (pintype "passive"))
      (node (ref "U1") (pin "120") (pinfunction "VSS_120") (pintype "passive"))
      (node (ref "U1") (pin "121") (pinfunction "VDD_121") (pintype "passive"))
      (node (ref "U1") (pin "130") (pinfunction "VSS_130") (pintype "passive"))
      (node (ref "U1") (pin "131") (pinfunction "VDD_131") (pintype "passive"))
      (node (ref "U1") (pin "143") (pinfunction "PDR_ON_143") (pintype "passive"))
      (node (ref "U1") (pin "144") (pinfunction "VDD_144") (pintype "passive"))
      (node (ref "U1") (pin "16") (pinfunction "VSS_16") (pintype "passive"))
      (node (ref "U1") (pin "17") (pinfunction "VDD_17") (pintype "passive"))
      (node (ref "U1") (pin "30") (pinfunction "VDD_30") (pintype "passive"))
      (node (ref "U1") (pin "31") (pinfunction "VSSA_31") (pintype "passive"))
      (node (ref "U1") (pin "33") (pinfunction "VDDA_33") (pintype "passive"))
      (node (ref "U1") (pin "38") (pinfunction "VSS_38") (pintype "passive"))
      (node (ref "U1") (pin "39") (pinfunction "VDD_39") (pintype "passive"))
      (node (ref "U1") (pin "51") (pinfunction "VSS_51") (pintype "passive"))
      (node (ref "U1") (pin "52") (pinfunction "VDD_52") (pintype "passive"))
      (node (ref "U1") (pin "61") (pinfunction "VSS_61") (pintype "passive"))
      (node (ref "U1") (pin "62") (pinfunction "VDD_62") (pintype "passive"))
      (node (ref "U1") (pin "66") (pinfunction "PE13/FSMC_D10/TIM1_CH3_66") (pintype "passive"))
      (node (ref "U1") (pin "67") (pinfunction "PE14/FSMC_D11/TIM1_CH4_67") (pintype "passive"))
      (node (ref "U1") (pin "72") (pinfunction "VDD_72") (pintype "passive"))
      (node (ref "U1") (pin "83") (pinfunction "VSS_83") (pintype "passive"))
      (node (ref "U1") (pin "84") (pinfunction "VDD_84") (pintype "passive"))
      (node (ref "U1") (pin "94") (pinfunction "VSS_94") (pintype "passive"))
      (node (ref "U1") (pin "95") (pinfunction "VDD_95") (pintype "passive"))
      (node (ref "U2") (pin "7") (pinfunction "GND_7") (pintype "passive"))
    )
    (net (code "43") (name "Net-(C6-Pad2)") (class "Default")
      (node (ref "C6") (pin "2") (pinfunction "2_2") (pintype "passive"))
      (node (ref "R20") (pin "1") (pinfunction "1_1") (pintype "passive"))
    )
    (net (code "44") (name "Net-(D1-K)") (class "Default")
      (node (ref "C2") (pin "2") (pinfunction "2_2") (pintype "passive"))
      (node (ref "D1") (pin "2") (pinfunction "K_2") (pintype "passive"))
      (node (ref "L1") (pin "2") (pinfunction "2_2") (pintype "passive"))
      (node (ref "U2") (pin "8") (pinfunction "PH_8") (pintype "passive"))
    )
    (net (code "45") (name "Net-(LED1-A)") (class "Default")
      (node (ref "LED1") (pin "1") (pinfunction "A_1") (pintype "passive"))
      (node (ref "R8") (pin "2") (pinfunction "2_2") (pintype "passive"))
    )
    (net (code "46") (name "Net-(LED2-A)") (class "Default")
      (node (ref "LED2") (pin "1") (pinfunction "A_1") (pintype "passive"))
      (node (ref "R9") (pin "2") (pinfunction "2_2") (pintype "passive"))
    )
    (net (code "47") (name "Net-(LEDS1-A)") (class "Default")
      (node (ref "LEDS1") (pin "1") (pinfunction "A_1") (pintype "passive"))
      (node (ref "R5") (pin "1") (pintype "passive"))
    )
    (net (code "48") (name "Net-(LEDS2-A)") (class "Default")
      (node (ref "LEDS2") (pin "1") (pinfunction "A_1") (pintype "passive"))
      (node (ref "R6") (pin "1") (pintype "passive"))
    )
    (net (code "49") (name "Net-(LEDS3-A)") (class "Default")
      (node (ref "LEDS3") (pin "1") (pinfunction "A_1") (pintype "passive"))
      (node (ref "R15") (pin "1") (pintype "passive"))
    )
    (net (code "50") (name "Net-(LEDS4-A)") (class "Default")
      (node (ref "LEDS4") (pin "1") (pinfunction "A_1") (pintype "passive"))
      (node (ref "R16") (pin "1") (pintype "passive"))
    )
    (net (code "51") (name "Net-(OP1-A)") (class "Default")
      (node (ref "OP1") (pin "1") (pinfunction "A_1") (pintype "passive"))
      (node (ref "R1") (pin "2") (pintype "passive"))
    )
    (net (code "52") (name "Net-(OP1-E)") (class "Default")
      (node (ref "OP1") (pin "3") (pinfunction "E_3") (pintype "passive"))
      (node (ref "R3") (pin "1") (pintype "passive"))
      (node (ref "R5") (pin "2") (pintype "passive"))
    )
    (net (code "53") (name "Net-(OP2-A)") (class "Default")
      (node (ref "OP2") (pin "1") (pinfunction "A_1") (pintype "passive"))
      (node (ref "R2") (pin "2") (pintype "passive"))
    )
    (net (code "54") (name "Net-(OP2-E)") (class "Default")
      (node (ref "OP2") (pin "3") (pinfunction "E_3") (pintype "passive"))
      (node (ref "R4") (pin "1") (pintype "passive"))
      (node (ref "R6") (pin "2") (pintype "passive"))
    )
    (net (code "55") (name "Net-(OP3-A)") (class "Default")
      (node (ref "OP3") (pin "1") (pinfunction "A_1") (pintype "passive"))
      (node (ref "R10") (pin "2") (pintype "passive"))
    )
    (net (code "56") (name "Net-(OP3-E)") (class "Default")
      (node (ref "OP3") (pin "3") (pinfunction "E_3") (pintype "passive"))
      (node (ref "R13") (pin "1") (pintype "passive"))
      (node (ref "R15") (pin "2") (pintype "passive"))
    )
    (net (code "57") (name "Net-(OP4-A)") (class "Default")
      (node (ref "OP4") (pin "1") (pinfunction "A_1") (pintype "passive"))
      (node (ref "R11") (pin "2") (pintype "passive"))
    )
    (net (code "58") (name "Net-(OP4-E)") (class "Default")
      (node (ref "OP4") (pin "3") (pinfunction "E_3") (pintype "passive"))
      (node (ref "R14") (pin "1") (pintype "passive"))
      (node (ref "R16") (pin "2") (pintype "passive"))
    )
    (net (code "59") (name "Net-(PWR1-A)") (class "Default")
      (node (ref "PWR1") (pin "1") (pinfunction "A_1") (pintype "passive"))
      (node (ref "R12") (pin "2") (pinfunction "2_2") (pintype "passive"))
    )
    (net (code "60") (name "Net-(SHINE1-A)") (class "Default")
      (node (ref "R7") (pin "2") (pinfunction "2_2") (pintype "passive"))
      (node (ref "SHINE1") (pin "1") (pinfunction "A_1") (pintype "passive"))
    )
    (net (code "61") (name "Net-(U1-PG10{slash}FSMC_NCE4_1{slash}FSMC_NE3)") (class "Default")
      (node (ref "C3") (pin "1") (pinfunction "1_1") (pintype "passive"))
      (node (ref "C4") (pin "1") (pinfunction "1_1") (pintype "passive"))
      (node (ref "C5") (pin "1") (pinfunction "1_1") (pintype "passive"))
      (node (ref "F1") (pin "2") (pinfunction "2_2") (pintype "passive"))
      (node (ref "R17") (pin "1") (pinfunction "1_1") (pintype "passive"))
      (node (ref "U1") (pin "125") (pinfunction "PG10/FSMC_NCE4_1/FSMC_NE3_125") (pintype "passive"))
      (node (ref "U2") (pin "2") (pinfunction "VIN_2") (pintype "passive"))
    )
    (net (code "62") (name "Net-(U1-PH0-OSC_IN)") (class "Default")
      (node (ref "C9") (pin "2") (pinfunction "2_2") (pintype "passive"))
      (node (ref "R24") (pin "2") (pinfunction "2_2") (pintype "passive"))
      (node (ref "U1") (pin "23") (pinfunction "PH0-OSC_IN_23") (pintype "passive"))
      (node (ref "X1") (pin "2") (pinfunction "OSC2_2") (pintype "passive"))
    )
    (net (code "63") (name "Net-(U1-PH1-OSC_OUT)") (class "Default")
      (node (ref "C10") (pin "2") (pinfunction "2_2") (pintype "passive"))
      (node (ref "R24") (pin "1") (pinfunction "1_1") (pintype "passive"))
      (node (ref "U1") (pin "24") (pinfunction "PH1-OSC_OUT_24") (pintype "passive"))
      (node (ref "X1") (pin "1") (pinfunction "OSC1_1") (pintype "passive"))
    )
    (net (code "64") (name "Net-(U1-Vcap_1)") (class "Default")
      (node (ref "C11") (pin "1") (pinfunction "1_1") (pintype "passive"))
      (node (ref "U1") (pin "71") (pinfunction "Vcap_1_71") (pintype "passive"))
    )
    (net (code "65") (name "Net-(U1-Vcap_2)") (class "Default")
      (node (ref "C12") (pin "1") (pinfunction "1_1") (pintype "passive"))
      (node (ref "U1") (pin "106") (pinfunction "Vcap_2_106") (pintype "passive"))
    )
    (net (code "66") (name "Net-(U2-BOOT)") (class "Default")
      (node (ref "C2") (pin "1") (pinfunction "1_1") (pintype "passive"))
      (node (ref "U2") (pin "1") (pinfunction "BOOT_1") (pintype "passive"))
    )
    (net (code "67") (name "Net-(U2-COMP)") (class "Default")
      (node (ref "C6") (pin "1") (pinfunction "1_1") (pintype "passive"))
      (node (ref "C7") (pin "1") (pinfunction "1_1") (pintype "passive"))
      (node (ref "U2") (pin "6") (pinfunction "COMP_6") (pintype "passive"))
    )
    (net (code "68") (name "Net-(U2-EN)") (class "Default")
      (node (ref "R17") (pin "2") (pinfunction "2_2") (pintype "passive"))
      (node (ref "R18") (pin "2") (pinfunction "2_2") (pintype "passive"))
      (node (ref "U2") (pin "3") (pinfunction "EN_3") (pintype "passive"))
    )
    (net (code "69") (name "Net-(U2-VSNS)") (class "Default")
      (node (ref "R19") (pin "1") (pinfunction "1_1") (pintype "passive"))
      (node (ref "R22") (pin "2") (pinfunction "2_2") (pintype "passive"))
      (node (ref "U2") (pin "5") (pinfunction "VSNS_5") (pintype "passive"))
    )
    (net (code "70") (name "VCC24") (class "Default")
      (node (ref "F1") (pin "1") (pinfunction "1_1") (pintype "passive"))
      (node (ref "OP1") (pin "4") (pinfunction "C_4") (pintype "passive"))
      (node (ref "OP3") (pin "4") (pinfunction "C_4") (pintype "passive"))
      (node (ref "P2") (pin "1") (pinfunction "1_1") (pintype "passive"))
    )
    (net (code "71") (name "unconnected-(U1-PA0-WKUP{slash}U2_CTS{slash}U4_TX{slash}ETH_MII_CRS{slash}TIM2_CH1_ETR{slash}TIM5_CH1{slash}TIM8_ETR{slash}ADC123_IN0-Pad34)") (class "Default")
      (node (ref "U1") (pin "34") (pinfunction "PA0-WKUP/U2_CTS/U4_TX/ETH_MII_CRS/TIM2_CH1_ETR/TIM5_CH1/TIM8_ETR/ADC123_IN0_34") (pintype "passive"))
    )
    (net (code "72") (name "unconnected-(U1-PA1{slash}U2_RTS{slash}U4_RX{slash}ETH_RMII_REF_CLK{slash}ETH_MII_RX_CLK{slash}TIM2_CH2{slash}TIM5_CH2{slash}ADC123_IN1-Pad35)") (class "Default")
      (node (ref "U1") (pin "35") (pinfunction "PA1/U2_RTS/U4_RX/ETH_RMII_REF_CLK/ETH_MII_RX_CLK/TIM2_CH2/TIM5_CH2/ADC123_IN1_35") (pintype "passive"))
    )
    (net (code "73") (name "unconnected-(U1-PA2{slash}U2_TX{slash}TIM2_CH3{slash}TIM5_CH3{slash}TIM9_CH1{slash}ETH_MDIO{slash}ADC123_IN2-Pad36)") (class "Default")
      (node (ref "U1") (pin "36") (pinfunction "PA2/U2_TX/TIM2_CH3/TIM5_CH3/TIM9_CH1/ETH_MDIO/ADC123_IN2_36") (pintype "passive"))
    )
    (net (code "74") (name "unconnected-(U1-PA3{slash}U2_RX{slash}TIM2_CH4{slash}TIM5_CH4{slash}TIM9_CH2{slash}OTG_HS_ULPI_D0{slash}ETH_MII_COL{slash}ADC123_IN3-Pad37)") (class "Default")
      (node (ref "U1") (pin "37") (pinfunction "PA3/U2_RX/TIM2_CH4/TIM5_CH4/TIM9_CH2/OTG_HS_ULPI_D0/ETH_MII_COL/ADC123_IN3_37") (pintype "passive"))
    )
    (net (code "75") (name "unconnected-(U1-PA5{slash}SPI1_SCK{slash}OTG_HS_ULPI_CK{slash}TIM2_CH1_ETR{slash}TIM8_CH1N{slash}DAC2_OUT{slash}ADC12_IN5-Pad41)") (class "Default")
      (node (ref "U1") (pin "41") (pinfunction "PA5/SPI1_SCK/OTG_HS_ULPI_CK/TIM2_CH1_ETR/TIM8_CH1N/DAC2_OUT/ADC12_IN5_41") (pintype "passive"))
    )
    (net (code "76") (name "unconnected-(U1-PA7{slash}SPI1_MOSI{slash}TIM1_CH1N{slash}TIM3_CH2{slash}TIM8_CH1N{slash}TIM14_CH1{slash}ETH_MII_RX_DV{slash}ETH_RMII_CRS_DV{slash}ADC12_IN7-Pad43)") (class "Default")
      (node (ref "U1") (pin "43") (pinfunction "PA7/SPI1_MOSI/TIM1_CH1N/TIM3_CH2/TIM8_CH1N/TIM14_CH1/ETH_MII_RX_DV/ETH_RMII_CRS_DV/ADC12_IN7_43") (pintype "passive"))
    )
    (net (code "77") (name "unconnected-(U1-PA11{slash}TIM1_CH4{slash}U1_CTS{slash}CAN1_RX{slash}OTG_FS_DM-Pad103)") (class "Default")
      (node (ref "U1") (pin "103") (pinfunction "PA11/TIM1_CH4/U1_CTS/CAN1_RX/OTG_FS_DM_103") (pintype "passive"))
    )
    (net (code "78") (name "unconnected-(U1-PA12{slash}TIM1_ETR{slash}U1_RTS{slash}CAN1_TX{slash}OTG_FS_DP-Pad104)") (class "Default")
      (node (ref "U1") (pin "104") (pinfunction "PA12/TIM1_ETR/U1_RTS/CAN1_TX/OTG_FS_DP_104") (pintype "passive"))
    )
    (net (code "79") (name "unconnected-(U1-PA15{slash}JTDI{slash}SPI1_NSS{slash}SPI3_NSS{slash}TIM2_CH1_ETR{slash}I2S3_WS-Pad110)") (class "Default")
      (node (ref "U1") (pin "110") (pinfunction "PA15/JTDI/SPI1_NSS/SPI3_NSS/TIM2_CH1_ETR/I2S3_WS_110") (pintype "passive"))
    )
    (net (code "80") (name "unconnected-(U1-PB0{slash}TIM1_CH2N{slash}TIM3_CH3{slash}TIM8_CH2N{slash}OTG_HS_ULPI_D1{slash}ETH_MII_RXD2{slash}ADC12_IN8-Pad46)") (class "Default")
      (node (ref "U1") (pin "46") (pinfunction "PB0/TIM1_CH2N/TIM3_CH3/TIM8_CH2N/OTG_HS_ULPI_D1/ETH_MII_RXD2/ADC12_IN8_46") (pintype "passive"))
    )
    (net (code "81") (name "unconnected-(U1-PB1{slash}TIM1_CH3N{slash}TIM3_CH4{slash}TIM8_CH3N{slash}OTG_HS_INTN{slash}ETH_MII_RXD3{slash}ADC12_IN9-Pad47)") (class "Default")
      (node (ref "U1") (pin "47") (pinfunction "PB1/TIM1_CH3N/TIM3_CH4/TIM8_CH3N/OTG_HS_INTN/ETH_MII_RXD3/ADC12_IN9_47") (pintype "passive"))
    )
    (net (code "82") (name "unconnected-(U1-PB3{slash}JTDO{slash}TRACESWO{slash}TIM2_CH2{slash}SPI1_SCK{slash}SPI3_SCK{slash}I2S3_CK-Pad133)") (class "Default")
      (node (ref "U1") (pin "133") (pinfunction "PB3/JTDO/TRACESWO/TIM2_CH2/SPI1_SCK/SPI3_SCK/I2S3_CK_133") (pintype "passive"))
    )
    (net (code "83") (name "unconnected-(U1-PB4{slash}JNTRST{slash}TIM3_CH1{slash}SPI1_MISO{slash}SPI3_MISO{slash}I2S3ext_SD-Pad134)") (class "Default")
      (node (ref "U1") (pin "134") (pinfunction "PB4/JNTRST/TIM3_CH1/SPI1_MISO/SPI3_MISO/I2S3ext_SD_134") (pintype "passive"))
    )
    (net (code "84") (name "unconnected-(U1-PB5{slash}TIM3_CH2{slash}SPI1_MOSI{slash}SPI3_MOSI{slash}CAN2_RX{slash}I2C1_SMBA{slash}OTG_HS_ULPI_D7{slash}ETH_PPS_OUT{slash}DCMI_D10{slash}I2S3_SD-Pad135)") (class "Default")
      (node (ref "U1") (pin "135") (pinfunction "PB5/TIM3_CH2/SPI1_MOSI/SPI3_MOSI/CAN2_RX/I2C1_SMBA/OTG_HS_ULPI_D7/ETH_PPS_OUT/DCMI_D10/I2S3_SD_135") (pintype "passive"))
    )
    (net (code "85") (name "unconnected-(U1-PB8{slash}TIM4_CH3{slash}TIM10_CH1{slash}CAN1_RX{slash}SDIO_D4{slash}ETH_MII_TXD3{slash}I2C1_SCL{slash}DCMI_D6-Pad139)") (class "Default")
      (node (ref "U1") (pin "139") (pinfunction "PB8/TIM4_CH3/TIM10_CH1/CAN1_RX/SDIO_D4/ETH_MII_TXD3/I2C1_SCL/DCMI_D6_139") (pintype "passive"))
    )
    (net (code "86") (name "unconnected-(U1-PB9{slash}TIM4_CH4{slash}TIM11_CH1{slash}CAN1_TX{slash}SDIO_D5{slash}SPI2_NSS{slash}I2C1_SDA{slash}DCMI_D7{slash}I2S2_WS-Pad140)") (class "Default")
      (node (ref "U1") (pin "140") (pinfunction "PB9/TIM4_CH4/TIM11_CH1/CAN1_TX/SDIO_D5/SPI2_NSS/I2C1_SDA/DCMI_D7/I2S2_WS_140") (pintype "passive"))
    )
    (net (code "87") (name "unconnected-(U1-PB10{slash}SPI2_SCK{slash}TIM2_CH3{slash}U3_TX{slash}I2C2_SCL{slash}OTG_HS_ULPI_D3{slash}I2S2_CK-Pad69)") (class "Default")
      (node (ref "U1") (pin "69") (pinfunction "PB10/SPI2_SCK/TIM2_CH3/U3_TX/I2C2_SCL/OTG_HS_ULPI_D3/I2S2_CK_69") (pintype "passive"))
    )
    (net (code "88") (name "unconnected-(U1-PB11{slash}TIM2_CH4{slash}U3_RX{slash}I2C2_SDA{slash}HS_ULPI_D4{slash}ETH_MII_TX_EN{slash}ETH_RMII_TX_EN-Pad70)") (class "Default")
      (node (ref "U1") (pin "70") (pinfunction "PB11/TIM2_CH4/U3_RX/I2C2_SDA/HS_ULPI_D4/ETH_MII_TX_EN/ETH_RMII_TX_EN_70") (pintype "passive"))
    )
    (net (code "89") (name "unconnected-(U1-PC0{slash}OTG_HS_ULPI_STP{slash}ADC123_IN10-Pad26)") (class "Default")
      (node (ref "U1") (pin "26") (pinfunction "PC0/OTG_HS_ULPI_STP/ADC123_IN10_26") (pintype "passive"))
    )
    (net (code "90") (name "unconnected-(U1-PC1{slash}ETH_MDC{slash}ADC123_IN11-Pad27)") (class "Default")
      (node (ref "U1") (pin "27") (pinfunction "PC1/ETH_MDC/ADC123_IN11_27") (pintype "passive"))
    )
    (net (code "91") (name "unconnected-(U1-PC2{slash}SPI2_MISO{slash}OTG_HS_ULPI_DIR{slash}ETH_MII_TXD2{slash}I2S2ext_SD{slash}ADC123_IN12-Pad28)") (class "Default")
      (node (ref "U1") (pin "28") (pinfunction "PC2/SPI2_MISO/OTG_HS_ULPI_DIR/ETH_MII_TXD2/I2S2ext_SD/ADC123_IN12_28") (pintype "passive"))
    )
    (net (code "92") (name "unconnected-(U1-PC3{slash}SPI2_MOSI{slash}OTG_HS_ULPI_NXT{slash}ETH_MII_TX_CLK{slash}I2S2_SD{slash}ADC123_IN13-Pad29)") (class "Default")
      (node (ref "U1") (pin "29") (pinfunction "PC3/SPI2_MOSI/OTG_HS_ULPI_NXT/ETH_MII_TX_CLK/I2S2_SD/ADC123_IN13_29") (pintype "passive"))
    )
    (net (code "93") (name "unconnected-(U1-PC4{slash}ETH_MII_RXD0{slash}ETH_RMII_RXD0{slash}ADC12_IN14-Pad44)") (class "Default")
      (node (ref "U1") (pin "44") (pinfunction "PC4/ETH_MII_RXD0/ETH_RMII_RXD0/ADC12_IN14_44") (pintype "passive"))
    )
    (net (code "94") (name "unconnected-(U1-PC5{slash}ETH_MII_RXD1{slash}ETH_RMII_RXD1{slash}ADC12_IN15-Pad45)") (class "Default")
      (node (ref "U1") (pin "45") (pinfunction "PC5/ETH_MII_RXD1/ETH_RMII_RXD1/ADC12_IN15_45") (pintype "passive"))
    )
    (net (code "95") (name "unconnected-(U1-PC10{slash}SPI3_SCK{slash}U3_TX{slash}U4_TX{slash}SDIO_D2{slash}DCMI_D8{slash}I2S3_CK-Pad111)") (class "Default")
      (node (ref "U1") (pin "111") (pinfunction "PC10/SPI3_SCK/U3_TX/U4_TX/SDIO_D2/DCMI_D8/I2S3_CK_111") (pintype "passive"))
    )
    (net (code "96") (name "unconnected-(U1-PC12{slash}SPI3_MOSI{slash}U3_CK{slash}U5_TX{slash}SDIO_CK{slash}DCMI_D9{slash}I2S3_SD-Pad113)") (class "Default")
      (node (ref "U1") (pin "113") (pinfunction "PC12/SPI3_MOSI/U3_CK/U5_TX/SDIO_CK/DCMI_D9/I2S3_SD_113") (pintype "passive"))
    )
    (net (code "97") (name "unconnected-(U1-PC13{slash}RTC_AF1-Pad7)") (class "Default")
      (node (ref "U1") (pin "7") (pinfunction "PC13/RTC_AF1_7") (pintype "passive"))
    )
    (net (code "98") (name "unconnected-(U1-PC14-OSC32_IN-Pad8)") (class "Default")
      (node (ref "U1") (pin "8") (pinfunction "PC14-OSC32_IN_8") (pintype "passive"))
    )
    (net (code "99") (name "unconnected-(U1-PC15-OSC32_OUT-Pad9)") (class "Default")
      (node (ref "U1") (pin "9") (pinfunction "PC15-OSC32_OUT_9") (pintype "passive"))
    )
    (net (code "100") (name "unconnected-(U1-PD0{slash}FSMC_D2{slash}CAN1_RX-Pad114)") (class "Default")
      (node (ref "U1") (pin "114") (pinfunction "PD0/FSMC_D2/CAN1_RX_114") (pintype "passive"))
    )
    (net (code "101") (name "unconnected-(U1-PD1{slash}FSMC_D3{slash}CAN1_TX-Pad115)") (class "Default")
      (node (ref "U1") (pin "115") (pinfunction "PD1/FSMC_D3/CAN1_TX_115") (pintype "passive"))
    )
    (net (code "102") (name "unconnected-(U1-PD2{slash}TIM3_ETR{slash}U5_RX{slash}SDIO_CMD{slash}DCMI_D11-Pad116)") (class "Default")
      (node (ref "U1") (pin "116") (pinfunction "PD2/TIM3_ETR/U5_RX/SDIO_CMD/DCMI_D11_116") (pintype "passive"))
    )
    (net (code "103") (name "unconnected-(U1-PD3{slash}FSMC_CLK{slash}U2_CTS-Pad117)") (class "Default")
      (node (ref "U1") (pin "117") (pinfunction "PD3/FSMC_CLK/U2_CTS_117") (pintype "passive"))
    )
    (net (code "104") (name "unconnected-(U1-PD4{slash}FSMC_NOE{slash}U2_RTS-Pad118)") (class "Default")
      (node (ref "U1") (pin "118") (pinfunction "PD4/FSMC_NOE/U2_RTS_118") (pintype "passive"))
    )
    (net (code "105") (name "unconnected-(U1-PD5{slash}FSMC_NWE{slash}U2_TX-Pad119)") (class "Default")
      (node (ref "U1") (pin "119") (pinfunction "PD5/FSMC_NWE/U2_TX_119") (pintype "passive"))
    )
    (net (code "106") (name "unconnected-(U1-PD8{slash}FSMC_D13{slash}U3_TX-Pad77)") (class "Default")
      (node (ref "U1") (pin "77") (pinfunction "PD8/FSMC_D13/U3_TX_77") (pintype "passive"))
    )
    (net (code "107") (name "unconnected-(U1-PD9{slash}FSMC_D14{slash}U3_RX-Pad78)") (class "Default")
      (node (ref "U1") (pin "78") (pinfunction "PD9/FSMC_D14/U3_RX_78") (pintype "passive"))
    )
    (net (code "108") (name "unconnected-(U1-PD10{slash}FSMC_D15{slash}U3_CK-Pad79)") (class "Default")
      (node (ref "U1") (pin "79") (pinfunction "PD10/FSMC_D15/U3_CK_79") (pintype "passive"))
    )
    (net (code "109") (name "unconnected-(U1-PD14{slash}FSMC_D0{slash}TIM4_CH3-Pad85)") (class "Default")
      (node (ref "U1") (pin "85") (pinfunction "PD14/FSMC_D0/TIM4_CH3_85") (pintype "passive"))
    )
    (net (code "110") (name "unconnected-(U1-PD15{slash}FSMC_D1{slash}TIM4_CH4-Pad86)") (class "Default")
      (node (ref "U1") (pin "86") (pinfunction "PD15/FSMC_D1/TIM4_CH4_86") (pintype "passive"))
    )
    (net (code "111") (name "unconnected-(U1-PE0{slash}TIM4_ETR{slash}FSMC_NBL0{slash}DCMI_D2-Pad141)") (class "Default")
      (node (ref "U1") (pin "141") (pinfunction "PE0/TIM4_ETR/FSMC_NBL0/DCMI_D2_141") (pintype "passive"))
    )
    (net (code "112") (name "unconnected-(U1-PE1{slash}FSMC_NBL1{slash}DCMI_D3-Pad142)") (class "Default")
      (node (ref "U1") (pin "142") (pinfunction "PE1/FSMC_NBL1/DCMI_D3_142") (pintype "passive"))
    )
    (net (code "113") (name "unconnected-(U1-PE2{slash}TRACECLK{slash}FSMC_A23{slash}ETH_MII_TXD3-Pad1)") (class "Default")
      (node (ref "U1") (pin "1") (pinfunction "PE2/TRACECLK/FSMC_A23/ETH_MII_TXD3_1") (pintype "passive"))
    )
    (net (code "114") (name "unconnected-(U1-PE3{slash}TRACED0{slash}FSMC_A19-Pad2)") (class "Default")
      (node (ref "U1") (pin "2") (pinfunction "PE3/TRACED0/FSMC_A19_2") (pintype "passive"))
    )
    (net (code "115") (name "unconnected-(U1-PE4{slash}TRACED1{slash}FSMC_A20{slash}DCMI_D4-Pad3)") (class "Default")
      (node (ref "U1") (pin "3") (pinfunction "PE4/TRACED1/FSMC_A20/DCMI_D4_3") (pintype "passive"))
    )
    (net (code "116") (name "unconnected-(U1-PE7{slash}FSMC_D4{slash}TIM1_ETR-Pad58)") (class "Default")
      (node (ref "U1") (pin "58") (pinfunction "PE7/FSMC_D4/TIM1_ETR_58") (pintype "passive"))
    )
    (net (code "117") (name "unconnected-(U1-PE8{slash}FSMC_D5{slash}TIM1_CH1N-Pad59)") (class "Default")
      (node (ref "U1") (pin "59") (pinfunction "PE8/FSMC_D5/TIM1_CH1N_59") (pintype "passive"))
    )
    (net (code "118") (name "unconnected-(U1-PE9{slash}FSMC_D6{slash}TIM1_CH1-Pad60)") (class "Default")
      (node (ref "U1") (pin "60") (pinfunction "PE9/FSMC_D6/TIM1_CH1_60") (pintype "passive"))
    )
    (net (code "119") (name "unconnected-(U1-PE10{slash}FSMC_D7{slash}TIM1_CH2N-Pad63)") (class "Default")
      (node (ref "U1") (pin "63") (pinfunction "PE10/FSMC_D7/TIM1_CH2N_63") (pintype "passive"))
    )
    (net (code "120") (name "unconnected-(U1-PE11{slash}FSMC_D8{slash}TIM1_CH2-Pad64)") (class "Default")
      (node (ref "U1") (pin "64") (pinfunction "PE11/FSMC_D8/TIM1_CH2_64") (pintype "passive"))
    )
    (net (code "121") (name "unconnected-(U1-PF2{slash}FSMC_A2{slash}I2C2_SMBA-Pad12)") (class "Default")
      (node (ref "U1") (pin "12") (pinfunction "PF2/FSMC_A2/I2C2_SMBA_12") (pintype "passive"))
    )
    (net (code "122") (name "unconnected-(U1-PF3{slash}FSMC_A3{slash}ADC3_IN9-Pad13)") (class "Default")
      (node (ref "U1") (pin "13") (pinfunction "PF3/FSMC_A3/ADC3_IN9_13") (pintype "passive"))
    )
    (net (code "123") (name "unconnected-(U1-PF4{slash}FSMC_A4{slash}ADC3_IN14-Pad14)") (class "Default")
      (node (ref "U1") (pin "14") (pinfunction "PF4/FSMC_A4/ADC3_IN14_14") (pintype "passive"))
    )
    (net (code "124") (name "unconnected-(U1-PF5{slash}FSMC_A5{slash}ADC3_IN15-Pad15)") (class "Default")
      (node (ref "U1") (pin "15") (pinfunction "PF5/FSMC_A5/ADC3_IN15_15") (pintype "passive"))
    )
    (net (code "125") (name "unconnected-(U1-PF6{slash}TIM10_CH1{slash}FSMC_NIORD{slash}ADC3_IN4-Pad18)") (class "Default")
      (node (ref "U1") (pin "18") (pinfunction "PF6/TIM10_CH1/FSMC_NIORD/ADC3_IN4_18") (pintype "passive"))
    )
    (net (code "126") (name "unconnected-(U1-PF7{slash}TIM11_CH1{slash}FSMC_NREG{slash}ADC3_IN5-Pad19)") (class "Default")
      (node (ref "U1") (pin "19") (pinfunction "PF7/TIM11_CH1/FSMC_NREG/ADC3_IN5_19") (pintype "passive"))
    )
    (net (code "127") (name "unconnected-(U1-PF8{slash}TIM13_CH1{slash}FSMC_NIOWR{slash}ADC3_IN6-Pad20)") (class "Default")
      (node (ref "U1") (pin "20") (pinfunction "PF8/TIM13_CH1/FSMC_NIOWR/ADC3_IN6_20") (pintype "passive"))
    )
    (net (code "128") (name "unconnected-(U1-PF9{slash}TIM14_CH1{slash}FSMC_CD{slash}ADC3_IN7-Pad21)") (class "Default")
      (node (ref "U1") (pin "21") (pinfunction "PF9/TIM14_CH1/FSMC_CD/ADC3_IN7_21") (pintype "passive"))
    )
    (net (code "129") (name "unconnected-(U1-PF10{slash}FSMC_INTR{slash}ADC3_IN8-Pad22)") (class "Default")
      (node (ref "U1") (pin "22") (pinfunction "PF10/FSMC_INTR/ADC3_IN8_22") (pintype "passive"))
    )
    (net (code "130") (name "unconnected-(U1-PF11{slash}DCMI_D12-Pad49)") (class "Default")
      (node (ref "U1") (pin "49") (pinfunction "PF11/DCMI_D12_49") (pintype "passive"))
    )
    (net (code "131") (name "unconnected-(U1-PF12{slash}FSMC_A6-Pad50)") (class "Default")
      (node (ref "U1") (pin "50") (pinfunction "PF12/FSMC_A6_50") (pintype "passive"))
    )
    (net (code "132") (name "unconnected-(U1-PF13{slash}FSMC_A7-Pad53)") (class "Default")
      (node (ref "U1") (pin "53") (pinfunction "PF13/FSMC_A7_53") (pintype "passive"))
    )
    (net (code "133") (name "unconnected-(U1-PF14{slash}FSMC_A8-Pad54)") (class "Default")
      (node (ref "U1") (pin "54") (pinfunction "PF14/FSMC_A8_54") (pintype "passive"))
    )
    (net (code "134") (name "unconnected-(U1-PF15{slash}FSMC_A9-Pad55)") (class "Default")
      (node (ref "U1") (pin "55") (pinfunction "PF15/FSMC_A9_55") (pintype "passive"))
    )
    (net (code "135") (name "unconnected-(U1-PG0{slash}FSMC_A10-Pad56)") (class "Default")
      (node (ref "U1") (pin "56") (pinfunction "PG0/FSMC_A10_56") (pintype "passive"))
    )
    (net (code "136") (name "unconnected-(U1-PG1{slash}FSMC_A11-Pad57)") (class "Default")
      (node (ref "U1") (pin "57") (pinfunction "PG1/FSMC_A11_57") (pintype "passive"))
    )
    (net (code "137") (name "unconnected-(U1-PG2{slash}FSMC_A12-Pad87)") (class "Default")
      (node (ref "U1") (pin "87") (pinfunction "PG2/FSMC_A12_87") (pintype "passive"))
    )
    (net (code "138") (name "unconnected-(U1-PG3{slash}FSMC_A13-Pad88)") (class "Default")
      (node (ref "U1") (pin "88") (pinfunction "PG3/FSMC_A13_88") (pintype "passive"))
    )
    (net (code "139") (name "unconnected-(U1-PG4{slash}FSMC_A14-Pad89)") (class "Default")
      (node (ref "U1") (pin "89") (pinfunction "PG4/FSMC_A14_89") (pintype "passive"))
    )
    (net (code "140") (name "unconnected-(U1-PG5{slash}FSMC_A15-Pad90)") (class "Default")
      (node (ref "U1") (pin "90") (pinfunction "PG5/FSMC_A15_90") (pintype "passive"))
    )
    (net (code "141") (name "unconnected-(U1-PG6{slash}FSMC_INT2-Pad91)") (class "Default")
      (node (ref "U1") (pin "91") (pinfunction "PG6/FSMC_INT2_91") (pintype "passive"))
    )
    (net (code "142") (name "unconnected-(U1-PG7{slash}FSMC_INT3{slash}U6_CK-Pad92)") (class "Default")
      (node (ref "U1") (pin "92") (pinfunction "PG7/FSMC_INT3/U6_CK_92") (pintype "passive"))
    )
    (net (code "143") (name "unconnected-(U1-PG8{slash}U6_RTS{slash}ETH_PPS_OUT-Pad93)") (class "Default")
      (node (ref "U1") (pin "93") (pinfunction "PG8/U6_RTS/ETH_PPS_OUT_93") (pintype "passive"))
    )
    (net (code "144") (name "unconnected-(U1-PG11{slash}FSMC_NCE4_2{slash}ETH_MII_TX_EN{slash}ETH_RMII_TX_EN-Pad126)") (class "Default")
      (node (ref "U1") (pin "126") (pinfunction "PG11/FSMC_NCE4_2/ETH_MII_TX_EN/ETH_RMII_TX_EN_126") (pintype "passive"))
    )
    (net (code "145") (name "unconnected-(U1-PG12{slash}FSMC_NE4{slash}U6_RTS-Pad127)") (class "Default")
      (node (ref "U1") (pin "127") (pinfunction "PG12/FSMC_NE4/U6_RTS_127") (pintype "passive"))
    )
    (net (code "146") (name "unconnected-(U1-PG13{slash}FSMC_A24{slash}U6_CTS{slash}ETH_MII_TXD0{slash}ETH_RMII_TXD0-Pad128)") (class "Default")
      (node (ref "U1") (pin "128") (pinfunction "PG13/FSMC_A24/U6_CTS/ETH_MII_TXD0/ETH_RMII_TXD0_128") (pintype "passive"))
    )
    (net (code "147") (name "unconnected-(U1-PG14{slash}FSMC_A25{slash}U6_TX{slash}ETH_MII_TXD1{slash}ETH_RMII_TXD1-Pad129)") (class "Default")
      (node (ref "U1") (pin "129") (pinfunction "PG14/FSMC_A25/U6_TX/ETH_MII_TXD1/ETH_RMII_TXD1_129") (pintype "passive"))
    )
    (net (code "148") (name "unconnected-(U1-VBAT-Pad6)") (class "Default")
      (node (ref "U1") (pin "6") (pinfunction "VBAT_6") (pintype "passive"))
    )
  )
)
